# portable_tpa6138a2.net
KiCad netlist of a schematic drawn in EAGLE
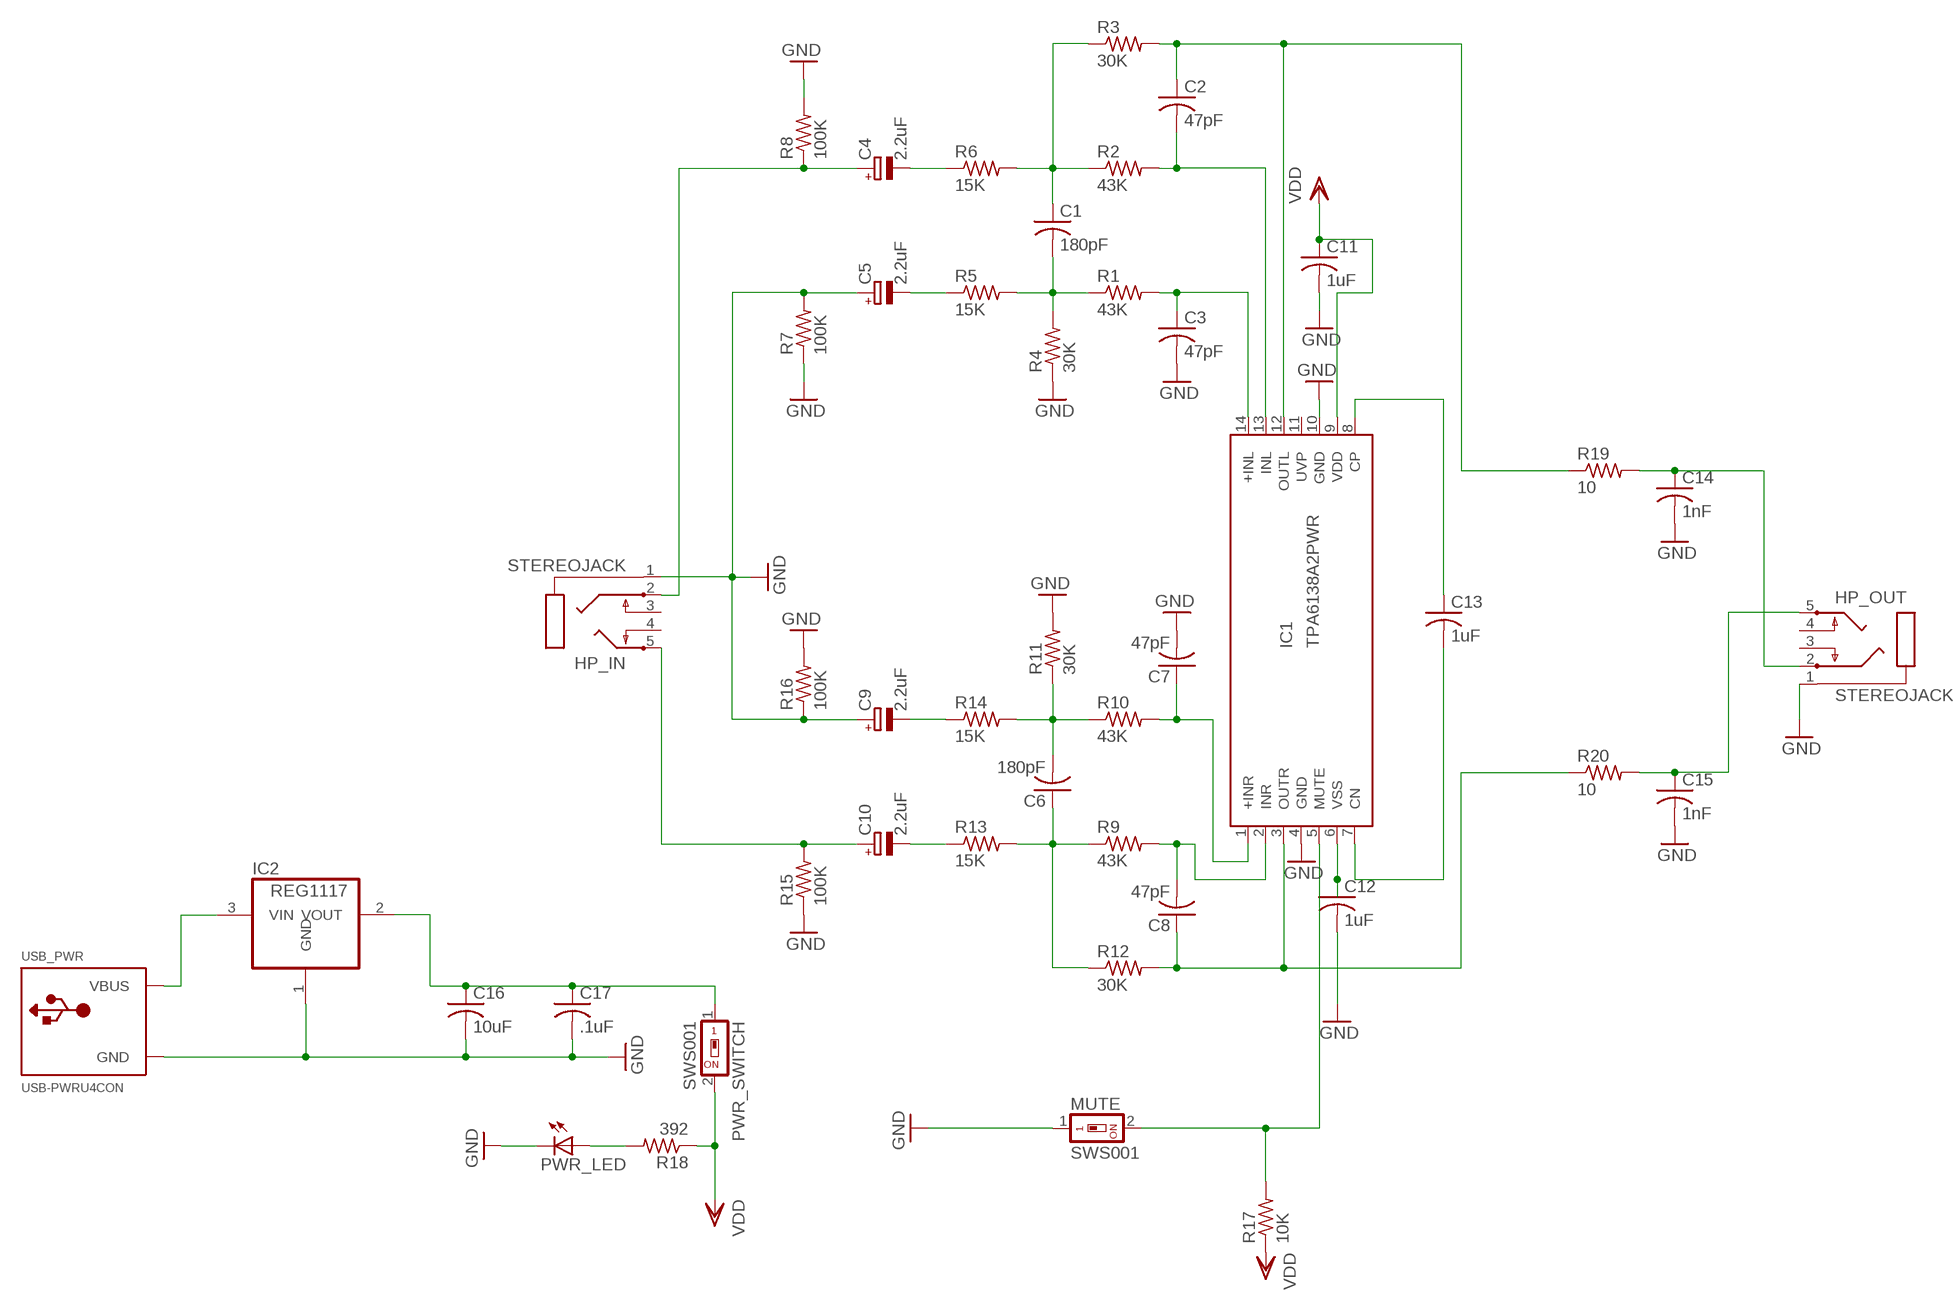
[diagram p0: schematic, sheet 1]

(export (version "E")
  (design (tool "Eeschema 10.0.6"))
  (components
    (comp (ref "C1")
      (value "180pF")
      (footprint "eagle-import:C0603")
      (libsource (lib "eagle-import") (part "C-USC0603"))
    )
    (comp (ref "C2")
      (value "47pF")
      (footprint "eagle-import:C0603")
      (libsource (lib "eagle-import") (part "C-USC0603"))
    )
    (comp (ref "C3")
      (value "47pF")
      (footprint "eagle-import:C0603")
      (libsource (lib "eagle-import") (part "C-USC0603"))
    )
    (comp (ref "C4")
      (value "2.2uF")
      (footprint "eagle-import:153CLV-0405")
      (libsource (lib "eagle-import") (part "CPOL-EU153CLV-0405"))
    )
    (comp (ref "C5")
      (value "2.2uF")
      (footprint "eagle-import:153CLV-0405")
      (libsource (lib "eagle-import") (part "CPOL-EU153CLV-0405"))
    )
    (comp (ref "C6")
      (value "180pF")
      (footprint "eagle-import:C0603")
      (libsource (lib "eagle-import") (part "C-USC0603"))
    )
    (comp (ref "C7")
      (value "47pF")
      (footprint "eagle-import:C0603")
      (libsource (lib "eagle-import") (part "C-USC0603"))
    )
    (comp (ref "C8")
      (value "47pF")
      (footprint "eagle-import:C0603")
      (libsource (lib "eagle-import") (part "C-USC0603"))
    )
    (comp (ref "C9")
      (value "2.2uF")
      (footprint "eagle-import:153CLV-0405")
      (libsource (lib "eagle-import") (part "CPOL-EU153CLV-0405"))
    )
    (comp (ref "C10")
      (value "2.2uF")
      (footprint "eagle-import:153CLV-0405")
      (libsource (lib "eagle-import") (part "CPOL-EU153CLV-0405"))
    )
    (comp (ref "C11")
      (value "1uF")
      (footprint "eagle-import:C0603")
      (libsource (lib "eagle-import") (part "C-USC0603"))
    )
    (comp (ref "C12")
      (value "1uF")
      (footprint "eagle-import:C0603")
      (libsource (lib "eagle-import") (part "C-USC0603"))
    )
    (comp (ref "C13")
      (value "1uF")
      (footprint "eagle-import:C0603")
      (libsource (lib "eagle-import") (part "C-USC0603"))
    )
    (comp (ref "C14")
      (value "1nF")
      (footprint "eagle-import:C0603")
      (libsource (lib "eagle-import") (part "C-USC0603"))
    )
    (comp (ref "C15")
      (value "1nF")
      (footprint "eagle-import:C0603")
      (libsource (lib "eagle-import") (part "C-USC0603"))
    )
    (comp (ref "C16")
      (value "10uF")
      (footprint "eagle-import:C0805")
      (libsource (lib "eagle-import") (part "C-USC0805"))
    )
    (comp (ref "C17")
      (value ".1uF")
      (footprint "eagle-import:C0603")
      (libsource (lib "eagle-import") (part "C-USC0603"))
    )
    (comp (ref "HP_IN")
      (value "STEREOJACK")
      (footprint "eagle-import:STX3100")
      (libsource (lib "eagle-import") (part "STEREOJACK"))
    )
    (comp (ref "HP_OUT")
      (value "STEREOJACK")
      (footprint "eagle-import:STX3100")
      (libsource (lib "eagle-import") (part "STEREOJACK"))
    )
    (comp (ref "IC1")
      (value "TPA6138A2PWR")
      (footprint "eagle-import:TSSOP14")
      (libsource (lib "eagle-import") (part "TPA6138A2PWR"))
    )
    (comp (ref "IC2")
      (value "REG1117")
      (footprint "eagle-import:SOT223")
      (libsource (lib "eagle-import") (part "REG1117"))
    )
    (comp (ref "MUTE")
      (value "SWS001")
      (footprint "eagle-import:SMS-001")
      (libsource (lib "eagle-import") (part "SWS001"))
    )
    (comp (ref "PWR_LED")
      (value "LED")
      (footprint "eagle-import:SMARTLED-TTW")
      (libsource (lib "eagle-import") (part "LED"))
    )
    (comp (ref "PWR_SWITCH")
      (value "SWS001")
      (footprint "eagle-import:SMS-001")
      (libsource (lib "eagle-import") (part "SWS001"))
    )
    (comp (ref "R1")
      (value "43K")
      (footprint "eagle-import:R0603")
      (libsource (lib "eagle-import") (part "R-US_R0603"))
    )
    (comp (ref "R2")
      (value "43K")
      (footprint "eagle-import:R0603")
      (libsource (lib "eagle-import") (part "R-US_R0603"))
    )
    (comp (ref "R3")
      (value "30K")
      (footprint "eagle-import:R0603")
      (libsource (lib "eagle-import") (part "R-US_R0603"))
    )
    (comp (ref "R4")
      (value "30K")
      (footprint "eagle-import:R0603")
      (libsource (lib "eagle-import") (part "R-US_R0603"))
    )
    (comp (ref "R5")
      (value "15K")
      (footprint "eagle-import:R0603")
      (libsource (lib "eagle-import") (part "R-US_R0603"))
    )
    (comp (ref "R6")
      (value "15K")
      (footprint "eagle-import:R0603")
      (libsource (lib "eagle-import") (part "R-US_R0603"))
    )
    (comp (ref "R7")
      (value "100K")
      (footprint "eagle-import:R0603")
      (libsource (lib "eagle-import") (part "R-US_R0603"))
    )
    (comp (ref "R8")
      (value "100K")
      (footprint "eagle-import:R0603")
      (libsource (lib "eagle-import") (part "R-US_R0603"))
    )
    (comp (ref "R9")
      (value "43K")
      (footprint "eagle-import:R0603")
      (libsource (lib "eagle-import") (part "R-US_R0603"))
    )
    (comp (ref "R10")
      (value "43K")
      (footprint "eagle-import:R0603")
      (libsource (lib "eagle-import") (part "R-US_R0603"))
    )
    (comp (ref "R11")
      (value "30K")
      (footprint "eagle-import:R0603")
      (libsource (lib "eagle-import") (part "R-US_R0603"))
    )
    (comp (ref "R12")
      (value "30K")
      (footprint "eagle-import:R0603")
      (libsource (lib "eagle-import") (part "R-US_R0603"))
    )
    (comp (ref "R13")
      (value "15K")
      (footprint "eagle-import:R0603")
      (libsource (lib "eagle-import") (part "R-US_R0603"))
    )
    (comp (ref "R14")
      (value "15K")
      (footprint "eagle-import:R0603")
      (libsource (lib "eagle-import") (part "R-US_R0603"))
    )
    (comp (ref "R15")
      (value "100K")
      (footprint "eagle-import:R0603")
      (libsource (lib "eagle-import") (part "R-US_R0603"))
    )
    (comp (ref "R16")
      (value "100K")
      (footprint "eagle-import:R0603")
      (libsource (lib "eagle-import") (part "R-US_R0603"))
    )
    (comp (ref "R17")
      (value "10K")
      (footprint "eagle-import:R0603")
      (libsource (lib "eagle-import") (part "R-US_R0603"))
    )
    (comp (ref "R18")
      (value "392")
      (footprint "eagle-import:R0603")
      (libsource (lib "eagle-import") (part "R-US_R0603"))
    )
    (comp (ref "R19")
      (value "10")
      (footprint "eagle-import:R0603")
      (libsource (lib "eagle-import") (part "R-US_R0603"))
    )
    (comp (ref "R20")
      (value "10")
      (footprint "eagle-import:R0603")
      (libsource (lib "eagle-import") (part "R-US_R0603"))
    )
    (comp (ref "USB_PWR")
      (value "USB-PWRU4CON")
      (footprint "eagle-import:USB-MINIB-THM-PWRONLY")
      (libsource (lib "eagle-import") (part "USB-PWRU4CON"))
    )
  )
  (nets
    (net (code "1") (name "GND") (class "Default")
      (node (ref "C11") (pin "2") (pinfunction "2_2") (pintype "passive"))
      (node (ref "C12") (pin "2") (pinfunction "2_2") (pintype "passive"))
      (node (ref "C14") (pin "2") (pinfunction "2_2") (pintype "passive"))
      (node (ref "C15") (pin "2") (pinfunction "2_2") (pintype "passive"))
      (node (ref "C16") (pin "2") (pinfunction "2_2") (pintype "passive"))
      (node (ref "C17") (pin "2") (pinfunction "2_2") (pintype "passive"))
      (node (ref "C3") (pin "2") (pinfunction "2_2") (pintype "passive"))
      (node (ref "C5") (pin "+") (pinfunction "+_+") (pintype "passive"))
      (node (ref "C7") (pin "2") (pinfunction "2_2") (pintype "passive"))
      (node (ref "C9") (pin "+") (pinfunction "+_+") (pintype "passive"))
      (node (ref "HP_IN") (pin "1") (pinfunction "1_1") (pintype "passive"))
      (node (ref "HP_OUT") (pin "1") (pinfunction "1_1") (pintype "passive"))
      (node (ref "IC1") (pin "10") (pinfunction "GND_10") (pintype "power_in"))
      (node (ref "IC1") (pin "4") (pinfunction "GND_4") (pintype "power_in"))
      (node (ref "IC2") (pin "1") (pinfunction "GND_1") (pintype "power_in"))
      (node (ref "MUTE") (pin "1") (pinfunction "1_1") (pintype "passive"))
      (node (ref "PWR_LED") (pin "C@1") (pinfunction "C_C@1") (pintype "passive"))
      (node (ref "R11") (pin "2") (pinfunction "2_2") (pintype "passive"))
      (node (ref "R15") (pin "1") (pinfunction "1_1") (pintype "passive"))
      (node (ref "R16") (pin "1") (pinfunction "1_1") (pintype "passive"))
      (node (ref "R16") (pin "2") (pinfunction "2_2") (pintype "passive"))
      (node (ref "R4") (pin "1") (pinfunction "1_1") (pintype "passive"))
      (node (ref "R7") (pin "1") (pinfunction "1_1") (pintype "passive"))
      (node (ref "R7") (pin "2") (pinfunction "2_2") (pintype "passive"))
      (node (ref "R8") (pin "2") (pinfunction "2_2") (pintype "passive"))
      (node (ref "USB_PWR") (pin "GND") (pinfunction "GND_GND") (pintype "power_in"))
    )
    (net (code "2") (name "Net-(C1-Pad1)") (class "Default")
      (node (ref "C1") (pin "1") (pinfunction "1_1") (pintype "passive"))
      (node (ref "R2") (pin "1") (pinfunction "1_1") (pintype "passive"))
      (node (ref "R3") (pin "1") (pinfunction "1_1") (pintype "passive"))
      (node (ref "R6") (pin "2") (pinfunction "2_2") (pintype "passive"))
    )
    (net (code "3") (name "Net-(C1-Pad2)") (class "Default")
      (node (ref "C1") (pin "2") (pinfunction "2_2") (pintype "passive"))
      (node (ref "R1") (pin "1") (pinfunction "1_1") (pintype "passive"))
      (node (ref "R4") (pin "2") (pinfunction "2_2") (pintype "passive"))
      (node (ref "R5") (pin "2") (pinfunction "2_2") (pintype "passive"))
    )
    (net (code "4") (name "Net-(C4-Pad+)") (class "Default")
      (node (ref "C4") (pin "+") (pinfunction "+_+") (pintype "passive"))
      (node (ref "HP_IN") (pin "2") (pinfunction "2_2") (pintype "passive"))
      (node (ref "R8") (pin "1") (pinfunction "1_1") (pintype "passive"))
    )
    (net (code "5") (name "Net-(C4-Pad-)") (class "Default")
      (node (ref "C4") (pin "-") (pinfunction "-_-") (pintype "passive"))
      (node (ref "R6") (pin "1") (pinfunction "1_1") (pintype "passive"))
    )
    (net (code "6") (name "Net-(C5-Pad-)") (class "Default")
      (node (ref "C5") (pin "-") (pinfunction "-_-") (pintype "passive"))
      (node (ref "R5") (pin "1") (pinfunction "1_1") (pintype "passive"))
    )
    (net (code "7") (name "Net-(C6-Pad1)") (class "Default")
      (node (ref "C6") (pin "1") (pinfunction "1_1") (pintype "passive"))
      (node (ref "R12") (pin "1") (pinfunction "1_1") (pintype "passive"))
      (node (ref "R13") (pin "2") (pinfunction "2_2") (pintype "passive"))
      (node (ref "R9") (pin "1") (pinfunction "1_1") (pintype "passive"))
    )
    (net (code "8") (name "Net-(C6-Pad2)") (class "Default")
      (node (ref "C6") (pin "2") (pinfunction "2_2") (pintype "passive"))
      (node (ref "R10") (pin "1") (pinfunction "1_1") (pintype "passive"))
      (node (ref "R11") (pin "1") (pinfunction "1_1") (pintype "passive"))
      (node (ref "R14") (pin "2") (pinfunction "2_2") (pintype "passive"))
    )
    (net (code "9") (name "Net-(C9-Pad-)") (class "Default")
      (node (ref "C9") (pin "-") (pinfunction "-_-") (pintype "passive"))
      (node (ref "R14") (pin "1") (pinfunction "1_1") (pintype "passive"))
    )
    (net (code "10") (name "Net-(C10-Pad+)") (class "Default")
      (node (ref "C10") (pin "+") (pinfunction "+_+") (pintype "passive"))
      (node (ref "HP_IN") (pin "5") (pinfunction "5_5") (pintype "passive"))
      (node (ref "R15") (pin "2") (pinfunction "2_2") (pintype "passive"))
    )
    (net (code "11") (name "Net-(C10-Pad-)") (class "Default")
      (node (ref "C10") (pin "-") (pinfunction "-_-") (pintype "passive"))
      (node (ref "R13") (pin "1") (pinfunction "1_1") (pintype "passive"))
    )
    (net (code "12") (name "Net-(C14-Pad1)") (class "Default")
      (node (ref "C14") (pin "1") (pinfunction "1_1") (pintype "passive"))
      (node (ref "HP_OUT") (pin "2") (pinfunction "2_2") (pintype "passive"))
      (node (ref "R19") (pin "2") (pinfunction "2_2") (pintype "passive"))
    )
    (net (code "13") (name "Net-(C15-Pad1)") (class "Default")
      (node (ref "C15") (pin "1") (pinfunction "1_1") (pintype "passive"))
      (node (ref "HP_OUT") (pin "5") (pinfunction "5_5") (pintype "passive"))
      (node (ref "R20") (pin "2") (pinfunction "2_2") (pintype "passive"))
    )
    (net (code "14") (name "Net-(IC1-+INL)") (class "Default")
      (node (ref "C3") (pin "1") (pinfunction "1_1") (pintype "passive"))
      (node (ref "IC1") (pin "14") (pinfunction "+INL_14") (pintype "input"))
      (node (ref "R1") (pin "2") (pinfunction "2_2") (pintype "passive"))
    )
    (net (code "15") (name "Net-(IC1-+INR)") (class "Default")
      (node (ref "C7") (pin "1") (pinfunction "1_1") (pintype "passive"))
      (node (ref "IC1") (pin "1") (pinfunction "+INR_1") (pintype "input"))
      (node (ref "R10") (pin "2") (pinfunction "2_2") (pintype "passive"))
    )
    (net (code "16") (name "Net-(IC1-CN)") (class "Default")
      (node (ref "C13") (pin "2") (pinfunction "2_2") (pintype "passive"))
      (node (ref "IC1") (pin "7") (pinfunction "CN_7") (pintype "bidirectional"))
    )
    (net (code "17") (name "Net-(IC1-CP)") (class "Default")
      (node (ref "C13") (pin "1") (pinfunction "1_1") (pintype "passive"))
      (node (ref "IC1") (pin "8") (pinfunction "CP_8") (pintype "bidirectional"))
    )
    (net (code "18") (name "Net-(IC1-INL)") (class "Default")
      (node (ref "C2") (pin "2") (pinfunction "2_2") (pintype "passive"))
      (node (ref "IC1") (pin "13") (pinfunction "INL_13") (pintype "input"))
      (node (ref "R2") (pin "2") (pinfunction "2_2") (pintype "passive"))
    )
    (net (code "19") (name "Net-(IC1-INR)") (class "Default")
      (node (ref "C8") (pin "2") (pinfunction "2_2") (pintype "passive"))
      (node (ref "IC1") (pin "2") (pinfunction "INR_2") (pintype "input"))
      (node (ref "R9") (pin "2") (pinfunction "2_2") (pintype "passive"))
    )
    (net (code "20") (name "Net-(IC1-MUTE)") (class "Default")
      (node (ref "IC1") (pin "5") (pinfunction "MUTE_5") (pintype "input"))
      (node (ref "MUTE") (pin "2") (pinfunction "2_2") (pintype "passive"))
      (node (ref "R17") (pin "2") (pinfunction "2_2") (pintype "passive"))
    )
    (net (code "21") (name "Net-(IC1-OUTL)") (class "Default")
      (node (ref "C2") (pin "1") (pinfunction "1_1") (pintype "passive"))
      (node (ref "IC1") (pin "12") (pinfunction "OUTL_12") (pintype "output"))
      (node (ref "R19") (pin "1") (pinfunction "1_1") (pintype "passive"))
      (node (ref "R3") (pin "2") (pinfunction "2_2") (pintype "passive"))
    )
    (net (code "22") (name "Net-(IC1-OUTR)") (class "Default")
      (node (ref "C8") (pin "1") (pinfunction "1_1") (pintype "passive"))
      (node (ref "IC1") (pin "3") (pinfunction "OUTR_3") (pintype "output"))
      (node (ref "R12") (pin "2") (pinfunction "2_2") (pintype "passive"))
      (node (ref "R20") (pin "1") (pinfunction "1_1") (pintype "passive"))
    )
    (net (code "23") (name "Net-(IC1-VSS)") (class "Default")
      (node (ref "C12") (pin "1") (pinfunction "1_1") (pintype "passive"))
      (node (ref "IC1") (pin "6") (pinfunction "VSS_6") (pintype "power_in"))
    )
    (net (code "24") (name "Net-(IC2-VIN)") (class "Default")
      (node (ref "IC2") (pin "3") (pinfunction "VIN_3") (pintype "input"))
      (node (ref "USB_PWR") (pin "VBUS") (pinfunction "VBUS_VBUS") (pintype "power_in"))
    )
    (net (code "25") (name "Net-(IC2-VOUT)") (class "Default")
      (node (ref "C16") (pin "1") (pinfunction "1_1") (pintype "passive"))
      (node (ref "C17") (pin "1") (pinfunction "1_1") (pintype "passive"))
      (node (ref "IC2") (pin "2") (pinfunction "VOUT_2") (pintype "output"))
      (node (ref "PWR_SWITCH") (pin "1") (pinfunction "1_1") (pintype "passive"))
    )
    (net (code "26") (name "Net-(PWR_LED-A)") (class "Default")
      (node (ref "PWR_LED") (pin "A@1") (pinfunction "A_A@1") (pintype "passive"))
      (node (ref "R18") (pin "2") (pinfunction "2_2") (pintype "passive"))
    )
    (net (code "27") (name "VDD") (class "Default")
      (node (ref "C11") (pin "1") (pinfunction "1_1") (pintype "passive"))
      (node (ref "IC1") (pin "9") (pinfunction "VDD_9") (pintype "power_in"))
      (node (ref "PWR_SWITCH") (pin "2") (pinfunction "2_2") (pintype "passive"))
      (node (ref "R17") (pin "1") (pinfunction "1_1") (pintype "passive"))
      (node (ref "R18") (pin "1") (pinfunction "1_1") (pintype "passive"))
    )
    (net (code "28") (name "unconnected-(HP_IN-Pad3)") (class "Default")
      (node (ref "HP_IN") (pin "3") (pinfunction "3_3") (pintype "passive"))
    )
    (net (code "29") (name "unconnected-(HP_IN-Pad4)") (class "Default")
      (node (ref "HP_IN") (pin "4") (pinfunction "4_4") (pintype "passive"))
    )
    (net (code "30") (name "unconnected-(HP_OUT-Pad3)") (class "Default")
      (node (ref "HP_OUT") (pin "3") (pinfunction "3_3") (pintype "passive"))
    )
    (net (code "31") (name "unconnected-(HP_OUT-Pad4)") (class "Default")
      (node (ref "HP_OUT") (pin "4") (pinfunction "4_4") (pintype "passive"))
    )
    (net (code "32") (name "unconnected-(IC1-UVP-Pad11)") (class "Default")
      (node (ref "IC1") (pin "11") (pinfunction "UVP_11") (pintype "input"))
    )
  )
)
